# Enable_Bus_Circuit.net
KiCad netlist of a schematic drawn in EAGLE
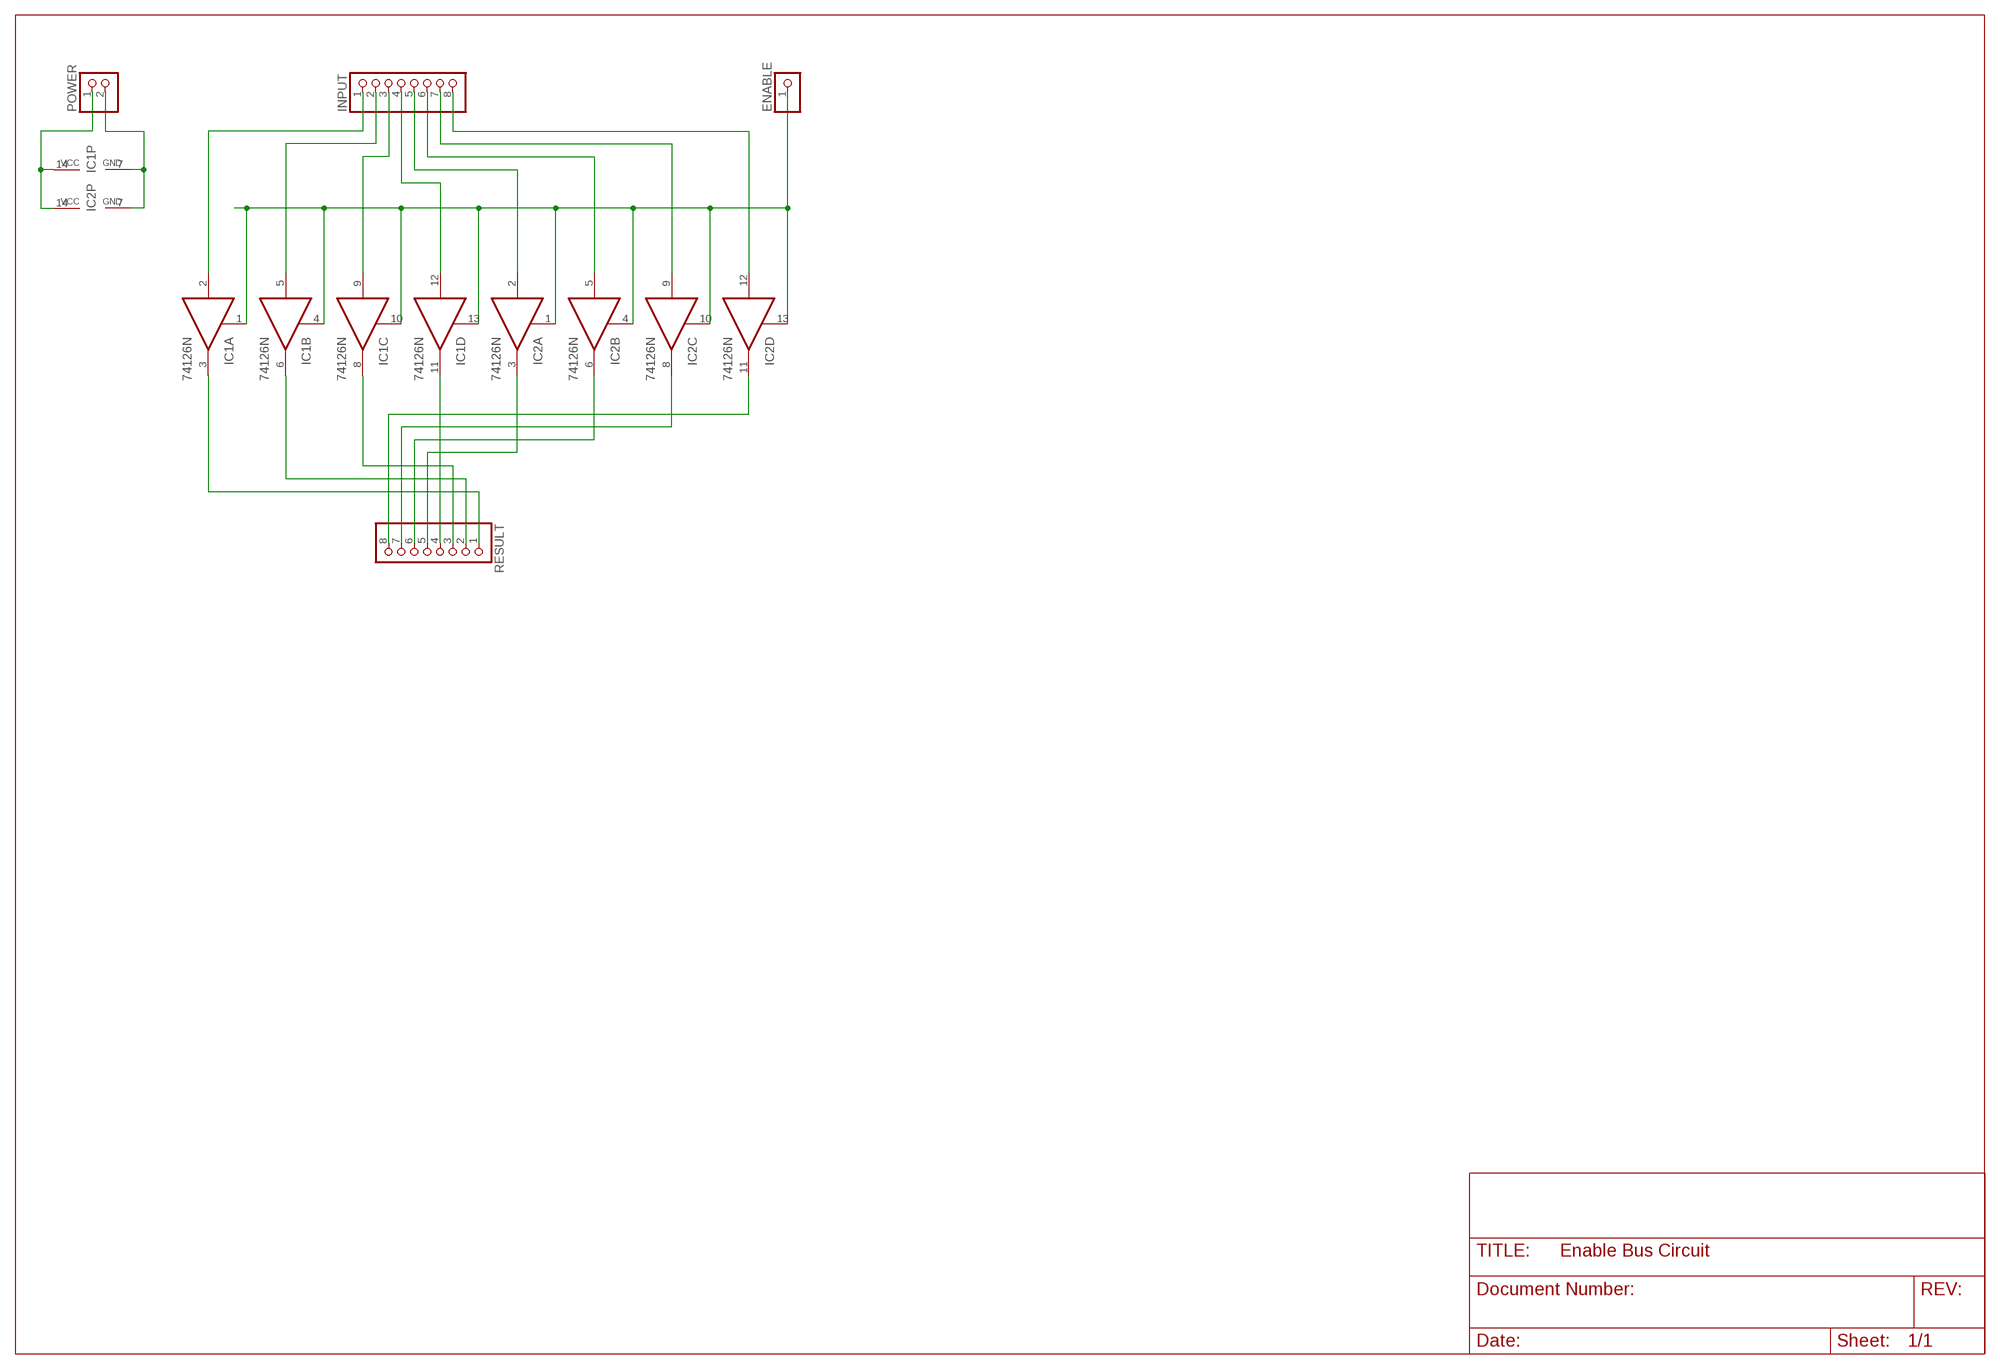
[diagram p0: schematic, sheet 1]

(export (version "E")
  (design (tool "Eeschema 10.0.6"))
  (components
    (comp (ref "ENABLE")
      (value "PINHD-1X1")
      (footprint "eagle-import:1X01")
      (libsource (lib "eagle-import") (part "PINHD-1X1"))
    )
    (comp (ref "IC1")
      (value "74126N")
      (footprint "eagle-import:DIL14")
      (libsource (lib "eagle-import") (part "74126N"))
    )
    (comp (ref "IC2")
      (value "74126N")
      (footprint "eagle-import:DIL14")
      (libsource (lib "eagle-import") (part "74126N"))
    )
    (comp (ref "INPUT")
      (value "PINHD-1X8")
      (footprint "eagle-import:1X08")
      (libsource (lib "eagle-import") (part "PINHD-1X8"))
    )
    (comp (ref "POWER")
      (value "PINHD-1X2")
      (footprint "eagle-import:1X02")
      (libsource (lib "eagle-import") (part "PINHD-1X2"))
    )
    (comp (ref "RESULT")
      (value "PINHD-1X8")
      (footprint "eagle-import:1X08")
      (libsource (lib "eagle-import") (part "PINHD-1X8"))
    )
  )
  (nets
    (net (code "1") (name "Net-(IC1A-I)") (class "Default")
      (node (ref "IC1") (pin "2") (pinfunction "I_2") (pintype "input"))
      (node (ref "INPUT") (pin "1") (pinfunction "1_1") (pintype "passive"))
    )
    (net (code "2") (name "Net-(IC1A-O)") (class "Default")
      (node (ref "IC1") (pin "3") (pinfunction "O_3") (pintype "output"))
      (node (ref "RESULT") (pin "1") (pinfunction "1_1") (pintype "passive"))
    )
    (net (code "3") (name "Net-(IC1A-OE)") (class "Default")
      (node (ref "ENABLE") (pin "1") (pinfunction "1_1") (pintype "passive"))
      (node (ref "IC1") (pin "1") (pinfunction "OE_1") (pintype "input"))
      (node (ref "IC1") (pin "10") (pinfunction "OE_10") (pintype "input"))
      (node (ref "IC1") (pin "13") (pinfunction "OE_13") (pintype "input"))
      (node (ref "IC1") (pin "4") (pinfunction "OE_4") (pintype "input"))
      (node (ref "IC2") (pin "1") (pinfunction "OE_1") (pintype "input"))
      (node (ref "IC2") (pin "10") (pinfunction "OE_10") (pintype "input"))
      (node (ref "IC2") (pin "13") (pinfunction "OE_13") (pintype "input"))
      (node (ref "IC2") (pin "4") (pinfunction "OE_4") (pintype "input"))
    )
    (net (code "4") (name "Net-(IC1B-I)") (class "Default")
      (node (ref "IC1") (pin "5") (pinfunction "I_5") (pintype "input"))
      (node (ref "INPUT") (pin "2") (pinfunction "2_2") (pintype "passive"))
    )
    (net (code "5") (name "Net-(IC1B-O)") (class "Default")
      (node (ref "IC1") (pin "6") (pinfunction "O_6") (pintype "output"))
      (node (ref "RESULT") (pin "2") (pinfunction "2_2") (pintype "passive"))
    )
    (net (code "6") (name "Net-(IC1C-I)") (class "Default")
      (node (ref "IC1") (pin "9") (pinfunction "I_9") (pintype "input"))
      (node (ref "INPUT") (pin "3") (pinfunction "3_3") (pintype "passive"))
    )
    (net (code "7") (name "Net-(IC1C-O)") (class "Default")
      (node (ref "IC1") (pin "8") (pinfunction "O_8") (pintype "output"))
      (node (ref "RESULT") (pin "3") (pinfunction "3_3") (pintype "passive"))
    )
    (net (code "8") (name "Net-(IC1D-I)") (class "Default")
      (node (ref "IC1") (pin "12") (pinfunction "I_12") (pintype "input"))
      (node (ref "INPUT") (pin "4") (pinfunction "4_4") (pintype "passive"))
    )
    (net (code "9") (name "Net-(IC1D-O)") (class "Default")
      (node (ref "IC1") (pin "11") (pinfunction "O_11") (pintype "output"))
      (node (ref "RESULT") (pin "4") (pinfunction "4_4") (pintype "passive"))
    )
    (net (code "10") (name "Net-(IC1E-GND)") (class "Default")
      (node (ref "IC1") (pin "7") (pinfunction "GND_7") (pintype "power_in"))
      (node (ref "IC2") (pin "7") (pinfunction "GND_7") (pintype "power_in"))
      (node (ref "POWER") (pin "2") (pinfunction "2_2") (pintype "passive"))
    )
    (net (code "11") (name "Net-(IC1E-VCC)") (class "Default")
      (node (ref "IC1") (pin "14") (pinfunction "VCC_14") (pintype "power_in"))
      (node (ref "IC2") (pin "14") (pinfunction "VCC_14") (pintype "power_in"))
      (node (ref "POWER") (pin "1") (pinfunction "1_1") (pintype "passive"))
    )
    (net (code "12") (name "Net-(IC2A-I)") (class "Default")
      (node (ref "IC2") (pin "2") (pinfunction "I_2") (pintype "input"))
      (node (ref "INPUT") (pin "5") (pinfunction "5_5") (pintype "passive"))
    )
    (net (code "13") (name "Net-(IC2A-O)") (class "Default")
      (node (ref "IC2") (pin "3") (pinfunction "O_3") (pintype "output"))
      (node (ref "RESULT") (pin "5") (pinfunction "5_5") (pintype "passive"))
    )
    (net (code "14") (name "Net-(IC2B-I)") (class "Default")
      (node (ref "IC2") (pin "5") (pinfunction "I_5") (pintype "input"))
      (node (ref "INPUT") (pin "6") (pinfunction "6_6") (pintype "passive"))
    )
    (net (code "15") (name "Net-(IC2B-O)") (class "Default")
      (node (ref "IC2") (pin "6") (pinfunction "O_6") (pintype "output"))
      (node (ref "RESULT") (pin "6") (pinfunction "6_6") (pintype "passive"))
    )
    (net (code "16") (name "Net-(IC2C-I)") (class "Default")
      (node (ref "IC2") (pin "9") (pinfunction "I_9") (pintype "input"))
      (node (ref "INPUT") (pin "7") (pinfunction "7_7") (pintype "passive"))
    )
    (net (code "17") (name "Net-(IC2C-O)") (class "Default")
      (node (ref "IC2") (pin "8") (pinfunction "O_8") (pintype "output"))
      (node (ref "RESULT") (pin "7") (pinfunction "7_7") (pintype "passive"))
    )
    (net (code "18") (name "Net-(IC2D-I)") (class "Default")
      (node (ref "IC2") (pin "12") (pinfunction "I_12") (pintype "input"))
      (node (ref "INPUT") (pin "8") (pinfunction "8_8") (pintype "passive"))
    )
    (net (code "19") (name "Net-(IC2D-O)") (class "Default")
      (node (ref "IC2") (pin "11") (pinfunction "O_11") (pintype "output"))
      (node (ref "RESULT") (pin "8") (pinfunction "8_8") (pintype "passive"))
    )
  )
)
